# backplane.net
KiCad netlist of a schematic drawn in EAGLE
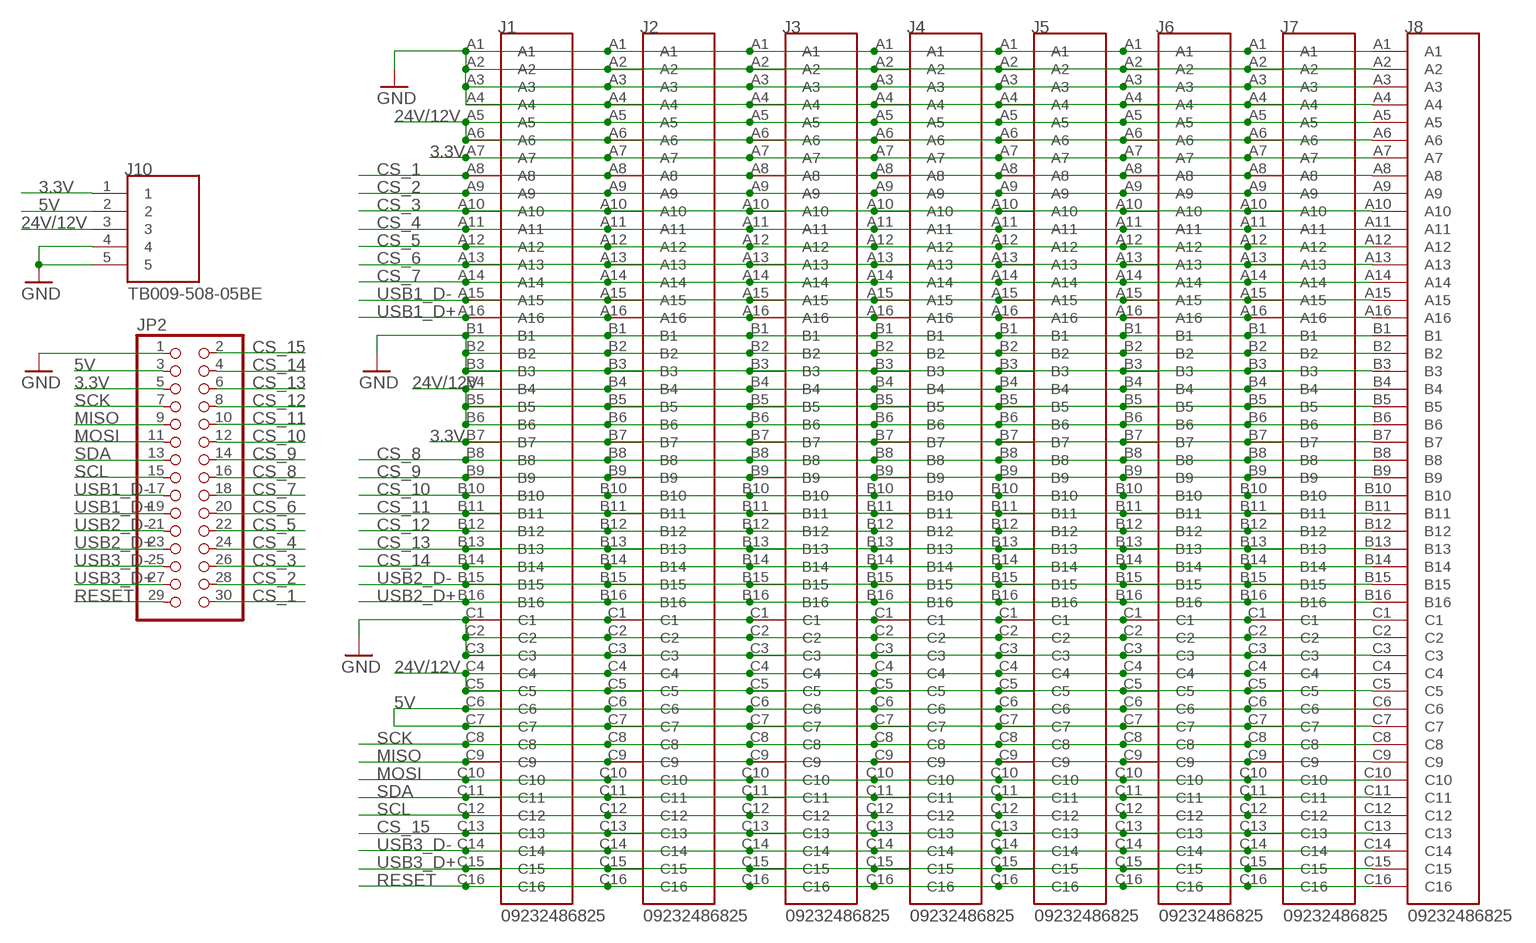
[diagram p0: schematic, sheet 1]

(export (version "E")
  (design (tool "Eeschema 10.0.6"))
  (components
    (comp (ref "J1")
      (value "09232486825")
      (footprint "eagle-import:HARTING_09232486825")
      (libsource (lib "eagle-import") (part "09232486825"))
    )
    (comp (ref "J2")
      (value "09232486825")
      (footprint "eagle-import:HARTING_09232486825")
      (libsource (lib "eagle-import") (part "09232486825"))
    )
    (comp (ref "J3")
      (value "09232486825")
      (footprint "eagle-import:HARTING_09232486825")
      (libsource (lib "eagle-import") (part "09232486825"))
    )
    (comp (ref "J4")
      (value "09232486825")
      (footprint "eagle-import:HARTING_09232486825")
      (libsource (lib "eagle-import") (part "09232486825"))
    )
    (comp (ref "J5")
      (value "09232486825")
      (footprint "eagle-import:HARTING_09232486825")
      (libsource (lib "eagle-import") (part "09232486825"))
    )
    (comp (ref "J6")
      (value "09232486825")
      (footprint "eagle-import:HARTING_09232486825")
      (libsource (lib "eagle-import") (part "09232486825"))
    )
    (comp (ref "J7")
      (value "09232486825")
      (footprint "eagle-import:HARTING_09232486825")
      (libsource (lib "eagle-import") (part "09232486825"))
    )
    (comp (ref "J8")
      (value "09232486825")
      (footprint "eagle-import:HARTING_09232486825")
      (libsource (lib "eagle-import") (part "09232486825"))
    )
    (comp (ref "J10")
      (value "TB009-508-05BE")
      (footprint "eagle-import:CUI_TB009-508-05BE")
      (libsource (lib "eagle-import") (part "TB009-508-05BE"))
    )
    (comp (ref "JP2")
      (value "PINHD-2X15")
      (footprint "eagle-import:2X15")
      (libsource (lib "eagle-import") (part "PINHD-2X15"))
    )
  )
  (nets
    (net (code "1") (name "/3.3V") (class "Default")
      (node (ref "J1") (pin "A7") (pinfunction "A7_A7") (pintype "passive"))
      (node (ref "J1") (pin "B7") (pinfunction "B7_B7") (pintype "passive"))
      (node (ref "J10") (pin "1") (pinfunction "1_1") (pintype "passive"))
      (node (ref "J2") (pin "A7") (pinfunction "A7_A7") (pintype "passive"))
      (node (ref "J2") (pin "B7") (pinfunction "B7_B7") (pintype "passive"))
      (node (ref "J3") (pin "A7") (pinfunction "A7_A7") (pintype "passive"))
      (node (ref "J3") (pin "B7") (pinfunction "B7_B7") (pintype "passive"))
      (node (ref "J4") (pin "A7") (pinfunction "A7_A7") (pintype "passive"))
      (node (ref "J4") (pin "B7") (pinfunction "B7_B7") (pintype "passive"))
      (node (ref "J5") (pin "A7") (pinfunction "A7_A7") (pintype "passive"))
      (node (ref "J5") (pin "B7") (pinfunction "B7_B7") (pintype "passive"))
      (node (ref "J6") (pin "A7") (pinfunction "A7_A7") (pintype "passive"))
      (node (ref "J6") (pin "B7") (pinfunction "B7_B7") (pintype "passive"))
      (node (ref "J7") (pin "A7") (pinfunction "A7_A7") (pintype "passive"))
      (node (ref "J7") (pin "B7") (pinfunction "B7_B7") (pintype "passive"))
      (node (ref "J8") (pin "A7") (pinfunction "A7_A7") (pintype "passive"))
      (node (ref "J8") (pin "B7") (pinfunction "B7_B7") (pintype "passive"))
      (node (ref "JP2") (pin "5") (pinfunction "5_5") (pintype "passive"))
    )
    (net (code "2") (name "/5V") (class "Default")
      (node (ref "J1") (pin "C6") (pinfunction "C6_C6") (pintype "passive"))
      (node (ref "J1") (pin "C7") (pinfunction "C7_C7") (pintype "passive"))
      (node (ref "J10") (pin "2") (pinfunction "2_2") (pintype "passive"))
      (node (ref "J2") (pin "C6") (pinfunction "C6_C6") (pintype "passive"))
      (node (ref "J2") (pin "C7") (pinfunction "C7_C7") (pintype "passive"))
      (node (ref "J3") (pin "C6") (pinfunction "C6_C6") (pintype "passive"))
      (node (ref "J3") (pin "C7") (pinfunction "C7_C7") (pintype "passive"))
      (node (ref "J4") (pin "C6") (pinfunction "C6_C6") (pintype "passive"))
      (node (ref "J4") (pin "C7") (pinfunction "C7_C7") (pintype "passive"))
      (node (ref "J5") (pin "C6") (pinfunction "C6_C6") (pintype "passive"))
      (node (ref "J5") (pin "C7") (pinfunction "C7_C7") (pintype "passive"))
      (node (ref "J6") (pin "C6") (pinfunction "C6_C6") (pintype "passive"))
      (node (ref "J6") (pin "C7") (pinfunction "C7_C7") (pintype "passive"))
      (node (ref "J7") (pin "C6") (pinfunction "C6_C6") (pintype "passive"))
      (node (ref "J7") (pin "C7") (pinfunction "C7_C7") (pintype "passive"))
      (node (ref "J8") (pin "C6") (pinfunction "C6_C6") (pintype "passive"))
      (node (ref "J8") (pin "C7") (pinfunction "C7_C7") (pintype "passive"))
      (node (ref "JP2") (pin "3") (pinfunction "3_3") (pintype "passive"))
    )
    (net (code "3") (name "/24V{slash}12V") (class "Default")
      (node (ref "J1") (pin "A5") (pinfunction "A5_A5") (pintype "passive"))
      (node (ref "J1") (pin "A6") (pinfunction "A6_A6") (pintype "passive"))
      (node (ref "J1") (pin "B4") (pinfunction "B4_B4") (pintype "passive"))
      (node (ref "J1") (pin "B5") (pinfunction "B5_B5") (pintype "passive"))
      (node (ref "J1") (pin "B6") (pinfunction "B6_B6") (pintype "passive"))
      (node (ref "J1") (pin "C4") (pinfunction "C4_C4") (pintype "passive"))
      (node (ref "J1") (pin "C5") (pinfunction "C5_C5") (pintype "passive"))
      (node (ref "J10") (pin "3") (pinfunction "3_3") (pintype "passive"))
      (node (ref "J2") (pin "A5") (pinfunction "A5_A5") (pintype "passive"))
      (node (ref "J2") (pin "A6") (pinfunction "A6_A6") (pintype "passive"))
      (node (ref "J2") (pin "B4") (pinfunction "B4_B4") (pintype "passive"))
      (node (ref "J2") (pin "B5") (pinfunction "B5_B5") (pintype "passive"))
      (node (ref "J2") (pin "B6") (pinfunction "B6_B6") (pintype "passive"))
      (node (ref "J2") (pin "C4") (pinfunction "C4_C4") (pintype "passive"))
      (node (ref "J2") (pin "C5") (pinfunction "C5_C5") (pintype "passive"))
      (node (ref "J3") (pin "A5") (pinfunction "A5_A5") (pintype "passive"))
      (node (ref "J3") (pin "A6") (pinfunction "A6_A6") (pintype "passive"))
      (node (ref "J3") (pin "B4") (pinfunction "B4_B4") (pintype "passive"))
      (node (ref "J3") (pin "B5") (pinfunction "B5_B5") (pintype "passive"))
      (node (ref "J3") (pin "B6") (pinfunction "B6_B6") (pintype "passive"))
      (node (ref "J3") (pin "C4") (pinfunction "C4_C4") (pintype "passive"))
      (node (ref "J3") (pin "C5") (pinfunction "C5_C5") (pintype "passive"))
      (node (ref "J4") (pin "A5") (pinfunction "A5_A5") (pintype "passive"))
      (node (ref "J4") (pin "A6") (pinfunction "A6_A6") (pintype "passive"))
      (node (ref "J4") (pin "B4") (pinfunction "B4_B4") (pintype "passive"))
      (node (ref "J4") (pin "B5") (pinfunction "B5_B5") (pintype "passive"))
      (node (ref "J4") (pin "B6") (pinfunction "B6_B6") (pintype "passive"))
      (node (ref "J4") (pin "C4") (pinfunction "C4_C4") (pintype "passive"))
      (node (ref "J4") (pin "C5") (pinfunction "C5_C5") (pintype "passive"))
      (node (ref "J5") (pin "A5") (pinfunction "A5_A5") (pintype "passive"))
      (node (ref "J5") (pin "A6") (pinfunction "A6_A6") (pintype "passive"))
      (node (ref "J5") (pin "B4") (pinfunction "B4_B4") (pintype "passive"))
      (node (ref "J5") (pin "B5") (pinfunction "B5_B5") (pintype "passive"))
      (node (ref "J5") (pin "B6") (pinfunction "B6_B6") (pintype "passive"))
      (node (ref "J5") (pin "C4") (pinfunction "C4_C4") (pintype "passive"))
      (node (ref "J5") (pin "C5") (pinfunction "C5_C5") (pintype "passive"))
      (node (ref "J6") (pin "A5") (pinfunction "A5_A5") (pintype "passive"))
      (node (ref "J6") (pin "A6") (pinfunction "A6_A6") (pintype "passive"))
      (node (ref "J6") (pin "B4") (pinfunction "B4_B4") (pintype "passive"))
      (node (ref "J6") (pin "B5") (pinfunction "B5_B5") (pintype "passive"))
      (node (ref "J6") (pin "B6") (pinfunction "B6_B6") (pintype "passive"))
      (node (ref "J6") (pin "C4") (pinfunction "C4_C4") (pintype "passive"))
      (node (ref "J6") (pin "C5") (pinfunction "C5_C5") (pintype "passive"))
      (node (ref "J7") (pin "A5") (pinfunction "A5_A5") (pintype "passive"))
      (node (ref "J7") (pin "A6") (pinfunction "A6_A6") (pintype "passive"))
      (node (ref "J7") (pin "B4") (pinfunction "B4_B4") (pintype "passive"))
      (node (ref "J7") (pin "B5") (pinfunction "B5_B5") (pintype "passive"))
      (node (ref "J7") (pin "B6") (pinfunction "B6_B6") (pintype "passive"))
      (node (ref "J7") (pin "C4") (pinfunction "C4_C4") (pintype "passive"))
      (node (ref "J7") (pin "C5") (pinfunction "C5_C5") (pintype "passive"))
      (node (ref "J8") (pin "A5") (pinfunction "A5_A5") (pintype "passive"))
      (node (ref "J8") (pin "A6") (pinfunction "A6_A6") (pintype "passive"))
      (node (ref "J8") (pin "B4") (pinfunction "B4_B4") (pintype "passive"))
      (node (ref "J8") (pin "B5") (pinfunction "B5_B5") (pintype "passive"))
      (node (ref "J8") (pin "B6") (pinfunction "B6_B6") (pintype "passive"))
      (node (ref "J8") (pin "C4") (pinfunction "C4_C4") (pintype "passive"))
      (node (ref "J8") (pin "C5") (pinfunction "C5_C5") (pintype "passive"))
    )
    (net (code "4") (name "/CS_1") (class "Default")
      (node (ref "J1") (pin "A8") (pinfunction "A8_A8") (pintype "passive"))
      (node (ref "J2") (pin "A8") (pinfunction "A8_A8") (pintype "passive"))
      (node (ref "J3") (pin "A8") (pinfunction "A8_A8") (pintype "passive"))
      (node (ref "J4") (pin "A8") (pinfunction "A8_A8") (pintype "passive"))
      (node (ref "J5") (pin "A8") (pinfunction "A8_A8") (pintype "passive"))
      (node (ref "J6") (pin "A8") (pinfunction "A8_A8") (pintype "passive"))
      (node (ref "J7") (pin "A8") (pinfunction "A8_A8") (pintype "passive"))
      (node (ref "J8") (pin "A8") (pinfunction "A8_A8") (pintype "passive"))
      (node (ref "JP2") (pin "30") (pinfunction "30_30") (pintype "passive"))
    )
    (net (code "5") (name "/CS_2") (class "Default")
      (node (ref "J1") (pin "A9") (pinfunction "A9_A9") (pintype "passive"))
      (node (ref "J2") (pin "A9") (pinfunction "A9_A9") (pintype "passive"))
      (node (ref "J3") (pin "A9") (pinfunction "A9_A9") (pintype "passive"))
      (node (ref "J4") (pin "A9") (pinfunction "A9_A9") (pintype "passive"))
      (node (ref "J5") (pin "A9") (pinfunction "A9_A9") (pintype "passive"))
      (node (ref "J6") (pin "A9") (pinfunction "A9_A9") (pintype "passive"))
      (node (ref "J7") (pin "A9") (pinfunction "A9_A9") (pintype "passive"))
      (node (ref "J8") (pin "A9") (pinfunction "A9_A9") (pintype "passive"))
      (node (ref "JP2") (pin "28") (pinfunction "28_28") (pintype "passive"))
    )
    (net (code "6") (name "/CS_3") (class "Default")
      (node (ref "J1") (pin "A10") (pinfunction "A10_A10") (pintype "passive"))
      (node (ref "J2") (pin "A10") (pinfunction "A10_A10") (pintype "passive"))
      (node (ref "J3") (pin "A10") (pinfunction "A10_A10") (pintype "passive"))
      (node (ref "J4") (pin "A10") (pinfunction "A10_A10") (pintype "passive"))
      (node (ref "J5") (pin "A10") (pinfunction "A10_A10") (pintype "passive"))
      (node (ref "J6") (pin "A10") (pinfunction "A10_A10") (pintype "passive"))
      (node (ref "J7") (pin "A10") (pinfunction "A10_A10") (pintype "passive"))
      (node (ref "J8") (pin "A10") (pinfunction "A10_A10") (pintype "passive"))
      (node (ref "JP2") (pin "26") (pinfunction "26_26") (pintype "passive"))
    )
    (net (code "7") (name "/CS_4") (class "Default")
      (node (ref "J1") (pin "A11") (pinfunction "A11_A11") (pintype "passive"))
      (node (ref "J2") (pin "A11") (pinfunction "A11_A11") (pintype "passive"))
      (node (ref "J3") (pin "A11") (pinfunction "A11_A11") (pintype "passive"))
      (node (ref "J4") (pin "A11") (pinfunction "A11_A11") (pintype "passive"))
      (node (ref "J5") (pin "A11") (pinfunction "A11_A11") (pintype "passive"))
      (node (ref "J6") (pin "A11") (pinfunction "A11_A11") (pintype "passive"))
      (node (ref "J7") (pin "A11") (pinfunction "A11_A11") (pintype "passive"))
      (node (ref "J8") (pin "A11") (pinfunction "A11_A11") (pintype "passive"))
      (node (ref "JP2") (pin "24") (pinfunction "24_24") (pintype "passive"))
    )
    (net (code "8") (name "/CS_5") (class "Default")
      (node (ref "J1") (pin "A12") (pinfunction "A12_A12") (pintype "passive"))
      (node (ref "J2") (pin "A12") (pinfunction "A12_A12") (pintype "passive"))
      (node (ref "J3") (pin "A12") (pinfunction "A12_A12") (pintype "passive"))
      (node (ref "J4") (pin "A12") (pinfunction "A12_A12") (pintype "passive"))
      (node (ref "J5") (pin "A12") (pinfunction "A12_A12") (pintype "passive"))
      (node (ref "J6") (pin "A12") (pinfunction "A12_A12") (pintype "passive"))
      (node (ref "J7") (pin "A12") (pinfunction "A12_A12") (pintype "passive"))
      (node (ref "J8") (pin "A12") (pinfunction "A12_A12") (pintype "passive"))
      (node (ref "JP2") (pin "22") (pinfunction "22_22") (pintype "passive"))
    )
    (net (code "9") (name "/CS_6") (class "Default")
      (node (ref "J1") (pin "A13") (pinfunction "A13_A13") (pintype "passive"))
      (node (ref "J2") (pin "A13") (pinfunction "A13_A13") (pintype "passive"))
      (node (ref "J3") (pin "A13") (pinfunction "A13_A13") (pintype "passive"))
      (node (ref "J4") (pin "A13") (pinfunction "A13_A13") (pintype "passive"))
      (node (ref "J5") (pin "A13") (pinfunction "A13_A13") (pintype "passive"))
      (node (ref "J6") (pin "A13") (pinfunction "A13_A13") (pintype "passive"))
      (node (ref "J7") (pin "A13") (pinfunction "A13_A13") (pintype "passive"))
      (node (ref "J8") (pin "A13") (pinfunction "A13_A13") (pintype "passive"))
      (node (ref "JP2") (pin "20") (pinfunction "20_20") (pintype "passive"))
    )
    (net (code "10") (name "/CS_7") (class "Default")
      (node (ref "J1") (pin "A14") (pinfunction "A14_A14") (pintype "passive"))
      (node (ref "J2") (pin "A14") (pinfunction "A14_A14") (pintype "passive"))
      (node (ref "J3") (pin "A14") (pinfunction "A14_A14") (pintype "passive"))
      (node (ref "J4") (pin "A14") (pinfunction "A14_A14") (pintype "passive"))
      (node (ref "J5") (pin "A14") (pinfunction "A14_A14") (pintype "passive"))
      (node (ref "J6") (pin "A14") (pinfunction "A14_A14") (pintype "passive"))
      (node (ref "J7") (pin "A14") (pinfunction "A14_A14") (pintype "passive"))
      (node (ref "J8") (pin "A14") (pinfunction "A14_A14") (pintype "passive"))
      (node (ref "JP2") (pin "18") (pinfunction "18_18") (pintype "passive"))
    )
    (net (code "11") (name "/CS_8") (class "Default")
      (node (ref "J1") (pin "B8") (pinfunction "B8_B8") (pintype "passive"))
      (node (ref "J2") (pin "B8") (pinfunction "B8_B8") (pintype "passive"))
      (node (ref "J3") (pin "B8") (pinfunction "B8_B8") (pintype "passive"))
      (node (ref "J4") (pin "B8") (pinfunction "B8_B8") (pintype "passive"))
      (node (ref "J5") (pin "B8") (pinfunction "B8_B8") (pintype "passive"))
      (node (ref "J6") (pin "B8") (pinfunction "B8_B8") (pintype "passive"))
      (node (ref "J7") (pin "B8") (pinfunction "B8_B8") (pintype "passive"))
      (node (ref "J8") (pin "B8") (pinfunction "B8_B8") (pintype "passive"))
      (node (ref "JP2") (pin "16") (pinfunction "16_16") (pintype "passive"))
    )
    (net (code "12") (name "/CS_9") (class "Default")
      (node (ref "J1") (pin "B9") (pinfunction "B9_B9") (pintype "passive"))
      (node (ref "J2") (pin "B9") (pinfunction "B9_B9") (pintype "passive"))
      (node (ref "J3") (pin "B9") (pinfunction "B9_B9") (pintype "passive"))
      (node (ref "J4") (pin "B9") (pinfunction "B9_B9") (pintype "passive"))
      (node (ref "J5") (pin "B9") (pinfunction "B9_B9") (pintype "passive"))
      (node (ref "J6") (pin "B9") (pinfunction "B9_B9") (pintype "passive"))
      (node (ref "J7") (pin "B9") (pinfunction "B9_B9") (pintype "passive"))
      (node (ref "J8") (pin "B9") (pinfunction "B9_B9") (pintype "passive"))
      (node (ref "JP2") (pin "14") (pinfunction "14_14") (pintype "passive"))
    )
    (net (code "13") (name "/CS_10") (class "Default")
      (node (ref "J1") (pin "B10") (pinfunction "B10_B10") (pintype "passive"))
      (node (ref "J2") (pin "B10") (pinfunction "B10_B10") (pintype "passive"))
      (node (ref "J3") (pin "B10") (pinfunction "B10_B10") (pintype "passive"))
      (node (ref "J4") (pin "B10") (pinfunction "B10_B10") (pintype "passive"))
      (node (ref "J5") (pin "B10") (pinfunction "B10_B10") (pintype "passive"))
      (node (ref "J6") (pin "B10") (pinfunction "B10_B10") (pintype "passive"))
      (node (ref "J7") (pin "B10") (pinfunction "B10_B10") (pintype "passive"))
      (node (ref "J8") (pin "B10") (pinfunction "B10_B10") (pintype "passive"))
      (node (ref "JP2") (pin "12") (pinfunction "12_12") (pintype "passive"))
    )
    (net (code "14") (name "/CS_11") (class "Default")
      (node (ref "J1") (pin "B11") (pinfunction "B11_B11") (pintype "passive"))
      (node (ref "J2") (pin "B11") (pinfunction "B11_B11") (pintype "passive"))
      (node (ref "J3") (pin "B11") (pinfunction "B11_B11") (pintype "passive"))
      (node (ref "J4") (pin "B11") (pinfunction "B11_B11") (pintype "passive"))
      (node (ref "J5") (pin "B11") (pinfunction "B11_B11") (pintype "passive"))
      (node (ref "J6") (pin "B11") (pinfunction "B11_B11") (pintype "passive"))
      (node (ref "J7") (pin "B11") (pinfunction "B11_B11") (pintype "passive"))
      (node (ref "J8") (pin "B11") (pinfunction "B11_B11") (pintype "passive"))
      (node (ref "JP2") (pin "10") (pinfunction "10_10") (pintype "passive"))
    )
    (net (code "15") (name "/CS_12") (class "Default")
      (node (ref "J1") (pin "B12") (pinfunction "B12_B12") (pintype "passive"))
      (node (ref "J2") (pin "B12") (pinfunction "B12_B12") (pintype "passive"))
      (node (ref "J3") (pin "B12") (pinfunction "B12_B12") (pintype "passive"))
      (node (ref "J4") (pin "B12") (pinfunction "B12_B12") (pintype "passive"))
      (node (ref "J5") (pin "B12") (pinfunction "B12_B12") (pintype "passive"))
      (node (ref "J6") (pin "B12") (pinfunction "B12_B12") (pintype "passive"))
      (node (ref "J7") (pin "B12") (pinfunction "B12_B12") (pintype "passive"))
      (node (ref "J8") (pin "B12") (pinfunction "B12_B12") (pintype "passive"))
      (node (ref "JP2") (pin "8") (pinfunction "8_8") (pintype "passive"))
    )
    (net (code "16") (name "/CS_13") (class "Default")
      (node (ref "J1") (pin "B13") (pinfunction "B13_B13") (pintype "passive"))
      (node (ref "J2") (pin "B13") (pinfunction "B13_B13") (pintype "passive"))
      (node (ref "J3") (pin "B13") (pinfunction "B13_B13") (pintype "passive"))
      (node (ref "J4") (pin "B13") (pinfunction "B13_B13") (pintype "passive"))
      (node (ref "J5") (pin "B13") (pinfunction "B13_B13") (pintype "passive"))
      (node (ref "J6") (pin "B13") (pinfunction "B13_B13") (pintype "passive"))
      (node (ref "J7") (pin "B13") (pinfunction "B13_B13") (pintype "passive"))
      (node (ref "J8") (pin "B13") (pinfunction "B13_B13") (pintype "passive"))
      (node (ref "JP2") (pin "6") (pinfunction "6_6") (pintype "passive"))
    )
    (net (code "17") (name "/CS_14") (class "Default")
      (node (ref "J1") (pin "B14") (pinfunction "B14_B14") (pintype "passive"))
      (node (ref "J2") (pin "B14") (pinfunction "B14_B14") (pintype "passive"))
      (node (ref "J3") (pin "B14") (pinfunction "B14_B14") (pintype "passive"))
      (node (ref "J4") (pin "B14") (pinfunction "B14_B14") (pintype "passive"))
      (node (ref "J5") (pin "B14") (pinfunction "B14_B14") (pintype "passive"))
      (node (ref "J6") (pin "B14") (pinfunction "B14_B14") (pintype "passive"))
      (node (ref "J7") (pin "B14") (pinfunction "B14_B14") (pintype "passive"))
      (node (ref "J8") (pin "B14") (pinfunction "B14_B14") (pintype "passive"))
      (node (ref "JP2") (pin "4") (pinfunction "4_4") (pintype "passive"))
    )
    (net (code "18") (name "/CS_15") (class "Default")
      (node (ref "J1") (pin "C13") (pinfunction "C13_C13") (pintype "passive"))
      (node (ref "J2") (pin "C13") (pinfunction "C13_C13") (pintype "passive"))
      (node (ref "J3") (pin "C13") (pinfunction "C13_C13") (pintype "passive"))
      (node (ref "J4") (pin "C13") (pinfunction "C13_C13") (pintype "passive"))
      (node (ref "J5") (pin "C13") (pinfunction "C13_C13") (pintype "passive"))
      (node (ref "J6") (pin "C13") (pinfunction "C13_C13") (pintype "passive"))
      (node (ref "J7") (pin "C13") (pinfunction "C13_C13") (pintype "passive"))
      (node (ref "J8") (pin "C13") (pinfunction "C13_C13") (pintype "passive"))
      (node (ref "JP2") (pin "2") (pinfunction "2_2") (pintype "passive"))
    )
    (net (code "19") (name "/MISO") (class "Default")
      (node (ref "J1") (pin "C9") (pinfunction "C9_C9") (pintype "passive"))
      (node (ref "J2") (pin "C9") (pinfunction "C9_C9") (pintype "passive"))
      (node (ref "J3") (pin "C9") (pinfunction "C9_C9") (pintype "passive"))
      (node (ref "J4") (pin "C9") (pinfunction "C9_C9") (pintype "passive"))
      (node (ref "J5") (pin "C9") (pinfunction "C9_C9") (pintype "passive"))
      (node (ref "J6") (pin "C9") (pinfunction "C9_C9") (pintype "passive"))
      (node (ref "J7") (pin "C9") (pinfunction "C9_C9") (pintype "passive"))
      (node (ref "J8") (pin "C9") (pinfunction "C9_C9") (pintype "passive"))
      (node (ref "JP2") (pin "9") (pinfunction "9_9") (pintype "passive"))
    )
    (net (code "20") (name "/MOSI") (class "Default")
      (node (ref "J1") (pin "C10") (pinfunction "C10_C10") (pintype "passive"))
      (node (ref "J2") (pin "C10") (pinfunction "C10_C10") (pintype "passive"))
      (node (ref "J3") (pin "C10") (pinfunction "C10_C10") (pintype "passive"))
      (node (ref "J4") (pin "C10") (pinfunction "C10_C10") (pintype "passive"))
      (node (ref "J5") (pin "C10") (pinfunction "C10_C10") (pintype "passive"))
      (node (ref "J6") (pin "C10") (pinfunction "C10_C10") (pintype "passive"))
      (node (ref "J7") (pin "C10") (pinfunction "C10_C10") (pintype "passive"))
      (node (ref "J8") (pin "C10") (pinfunction "C10_C10") (pintype "passive"))
      (node (ref "JP2") (pin "11") (pinfunction "11_11") (pintype "passive"))
    )
    (net (code "21") (name "/RESET") (class "Default")
      (node (ref "J1") (pin "C16") (pinfunction "C16_C16") (pintype "passive"))
      (node (ref "J2") (pin "C16") (pinfunction "C16_C16") (pintype "passive"))
      (node (ref "J3") (pin "C16") (pinfunction "C16_C16") (pintype "passive"))
      (node (ref "J4") (pin "C16") (pinfunction "C16_C16") (pintype "passive"))
      (node (ref "J5") (pin "C16") (pinfunction "C16_C16") (pintype "passive"))
      (node (ref "J6") (pin "C16") (pinfunction "C16_C16") (pintype "passive"))
      (node (ref "J7") (pin "C16") (pinfunction "C16_C16") (pintype "passive"))
      (node (ref "J8") (pin "C16") (pinfunction "C16_C16") (pintype "passive"))
      (node (ref "JP2") (pin "29") (pinfunction "29_29") (pintype "passive"))
    )
    (net (code "22") (name "/SCK") (class "Default")
      (node (ref "J1") (pin "C8") (pinfunction "C8_C8") (pintype "passive"))
      (node (ref "J2") (pin "C8") (pinfunction "C8_C8") (pintype "passive"))
      (node (ref "J3") (pin "C8") (pinfunction "C8_C8") (pintype "passive"))
      (node (ref "J4") (pin "C8") (pinfunction "C8_C8") (pintype "passive"))
      (node (ref "J5") (pin "C8") (pinfunction "C8_C8") (pintype "passive"))
      (node (ref "J6") (pin "C8") (pinfunction "C8_C8") (pintype "passive"))
      (node (ref "J7") (pin "C8") (pinfunction "C8_C8") (pintype "passive"))
      (node (ref "J8") (pin "C8") (pinfunction "C8_C8") (pintype "passive"))
      (node (ref "JP2") (pin "7") (pinfunction "7_7") (pintype "passive"))
    )
    (net (code "23") (name "/SCL") (class "Default")
      (node (ref "J1") (pin "C12") (pinfunction "C12_C12") (pintype "passive"))
      (node (ref "J2") (pin "C12") (pinfunction "C12_C12") (pintype "passive"))
      (node (ref "J3") (pin "C12") (pinfunction "C12_C12") (pintype "passive"))
      (node (ref "J4") (pin "C12") (pinfunction "C12_C12") (pintype "passive"))
      (node (ref "J5") (pin "C12") (pinfunction "C12_C12") (pintype "passive"))
      (node (ref "J6") (pin "C12") (pinfunction "C12_C12") (pintype "passive"))
      (node (ref "J7") (pin "C12") (pinfunction "C12_C12") (pintype "passive"))
      (node (ref "J8") (pin "C12") (pinfunction "C12_C12") (pintype "passive"))
      (node (ref "JP2") (pin "15") (pinfunction "15_15") (pintype "passive"))
    )
    (net (code "24") (name "/SDA") (class "Default")
      (node (ref "J1") (pin "C11") (pinfunction "C11_C11") (pintype "passive"))
      (node (ref "J2") (pin "C11") (pinfunction "C11_C11") (pintype "passive"))
      (node (ref "J3") (pin "C11") (pinfunction "C11_C11") (pintype "passive"))
      (node (ref "J4") (pin "C11") (pinfunction "C11_C11") (pintype "passive"))
      (node (ref "J5") (pin "C11") (pinfunction "C11_C11") (pintype "passive"))
      (node (ref "J6") (pin "C11") (pinfunction "C11_C11") (pintype "passive"))
      (node (ref "J7") (pin "C11") (pinfunction "C11_C11") (pintype "passive"))
      (node (ref "J8") (pin "C11") (pinfunction "C11_C11") (pintype "passive"))
      (node (ref "JP2") (pin "13") (pinfunction "13_13") (pintype "passive"))
    )
    (net (code "25") (name "/USB1_D+") (class "Default")
      (node (ref "J1") (pin "A16") (pinfunction "A16_A16") (pintype "passive"))
      (node (ref "J2") (pin "A16") (pinfunction "A16_A16") (pintype "passive"))
      (node (ref "J3") (pin "A16") (pinfunction "A16_A16") (pintype "passive"))
      (node (ref "J4") (pin "A16") (pinfunction "A16_A16") (pintype "passive"))
      (node (ref "J5") (pin "A16") (pinfunction "A16_A16") (pintype "passive"))
      (node (ref "J6") (pin "A16") (pinfunction "A16_A16") (pintype "passive"))
      (node (ref "J7") (pin "A16") (pinfunction "A16_A16") (pintype "passive"))
      (node (ref "J8") (pin "A16") (pinfunction "A16_A16") (pintype "passive"))
      (node (ref "JP2") (pin "19") (pinfunction "19_19") (pintype "passive"))
    )
    (net (code "26") (name "/USB1_D-") (class "Default")
      (node (ref "J1") (pin "A15") (pinfunction "A15_A15") (pintype "passive"))
      (node (ref "J2") (pin "A15") (pinfunction "A15_A15") (pintype "passive"))
      (node (ref "J3") (pin "A15") (pinfunction "A15_A15") (pintype "passive"))
      (node (ref "J4") (pin "A15") (pinfunction "A15_A15") (pintype "passive"))
      (node (ref "J5") (pin "A15") (pinfunction "A15_A15") (pintype "passive"))
      (node (ref "J6") (pin "A15") (pinfunction "A15_A15") (pintype "passive"))
      (node (ref "J7") (pin "A15") (pinfunction "A15_A15") (pintype "passive"))
      (node (ref "J8") (pin "A15") (pinfunction "A15_A15") (pintype "passive"))
      (node (ref "JP2") (pin "17") (pinfunction "17_17") (pintype "passive"))
    )
    (net (code "27") (name "/USB2_D+") (class "Default")
      (node (ref "J1") (pin "B16") (pinfunction "B16_B16") (pintype "passive"))
      (node (ref "J2") (pin "B16") (pinfunction "B16_B16") (pintype "passive"))
      (node (ref "J3") (pin "B16") (pinfunction "B16_B16") (pintype "passive"))
      (node (ref "J4") (pin "B16") (pinfunction "B16_B16") (pintype "passive"))
      (node (ref "J5") (pin "B16") (pinfunction "B16_B16") (pintype "passive"))
      (node (ref "J6") (pin "B16") (pinfunction "B16_B16") (pintype "passive"))
      (node (ref "J7") (pin "B16") (pinfunction "B16_B16") (pintype "passive"))
      (node (ref "J8") (pin "B16") (pinfunction "B16_B16") (pintype "passive"))
      (node (ref "JP2") (pin "23") (pinfunction "23_23") (pintype "passive"))
    )
    (net (code "28") (name "/USB2_D-") (class "Default")
      (node (ref "J1") (pin "B15") (pinfunction "B15_B15") (pintype "passive"))
      (node (ref "J2") (pin "B15") (pinfunction "B15_B15") (pintype "passive"))
      (node (ref "J3") (pin "B15") (pinfunction "B15_B15") (pintype "passive"))
      (node (ref "J4") (pin "B15") (pinfunction "B15_B15") (pintype "passive"))
      (node (ref "J5") (pin "B15") (pinfunction "B15_B15") (pintype "passive"))
      (node (ref "J6") (pin "B15") (pinfunction "B15_B15") (pintype "passive"))
      (node (ref "J7") (pin "B15") (pinfunction "B15_B15") (pintype "passive"))
      (node (ref "J8") (pin "B15") (pinfunction "B15_B15") (pintype "passive"))
      (node (ref "JP2") (pin "21") (pinfunction "21_21") (pintype "passive"))
    )
    (net (code "29") (name "/USB3_D+") (class "Default")
      (node (ref "J1") (pin "C15") (pinfunction "C15_C15") (pintype "passive"))
      (node (ref "J2") (pin "C15") (pinfunction "C15_C15") (pintype "passive"))
      (node (ref "J3") (pin "C15") (pinfunction "C15_C15") (pintype "passive"))
      (node (ref "J4") (pin "C15") (pinfunction "C15_C15") (pintype "passive"))
      (node (ref "J5") (pin "C15") (pinfunction "C15_C15") (pintype "passive"))
      (node (ref "J6") (pin "C15") (pinfunction "C15_C15") (pintype "passive"))
      (node (ref "J7") (pin "C15") (pinfunction "C15_C15") (pintype "passive"))
      (node (ref "J8") (pin "C15") (pinfunction "C15_C15") (pintype "passive"))
      (node (ref "JP2") (pin "27") (pinfunction "27_27") (pintype "passive"))
    )
    (net (code "30") (name "/USB3_D-") (class "Default")
      (node (ref "J1") (pin "C14") (pinfunction "C14_C14") (pintype "passive"))
      (node (ref "J2") (pin "C14") (pinfunction "C14_C14") (pintype "passive"))
      (node (ref "J3") (pin "C14") (pinfunction "C14_C14") (pintype "passive"))
      (node (ref "J4") (pin "C14") (pinfunction "C14_C14") (pintype "passive"))
      (node (ref "J5") (pin "C14") (pinfunction "C14_C14") (pintype "passive"))
      (node (ref "J6") (pin "C14") (pinfunction "C14_C14") (pintype "passive"))
      (node (ref "J7") (pin "C14") (pinfunction "C14_C14") (pintype "passive"))
      (node (ref "J8") (pin "C14") (pinfunction "C14_C14") (pintype "passive"))
      (node (ref "JP2") (pin "25") (pinfunction "25_25") (pintype "passive"))
    )
    (net (code "31") (name "GND") (class "Default")
      (node (ref "J1") (pin "A1") (pinfunction "A1_A1") (pintype "passive"))
      (node (ref "J1") (pin "A2") (pinfunction "A2_A2") (pintype "passive"))
      (node (ref "J1") (pin "A3") (pinfunction "A3_A3") (pintype "passive"))
      (node (ref "J1") (pin "A4") (pinfunction "A4_A4") (pintype "passive"))
      (node (ref "J1") (pin "B1") (pinfunction "B1_B1") (pintype "passive"))
      (node (ref "J1") (pin "B2") (pinfunction "B2_B2") (pintype "passive"))
      (node (ref "J1") (pin "B3") (pinfunction "B3_B3") (pintype "passive"))
      (node (ref "J1") (pin "C1") (pinfunction "C1_C1") (pintype "passive"))
      (node (ref "J1") (pin "C2") (pinfunction "C2_C2") (pintype "passive"))
      (node (ref "J1") (pin "C3") (pinfunction "C3_C3") (pintype "passive"))
      (node (ref "J10") (pin "4") (pinfunction "4_4") (pintype "passive"))
      (node (ref "J10") (pin "5") (pinfunction "5_5") (pintype "passive"))
      (node (ref "J2") (pin "A1") (pinfunction "A1_A1") (pintype "passive"))
      (node (ref "J2") (pin "A2") (pinfunction "A2_A2") (pintype "passive"))
      (node (ref "J2") (pin "A3") (pinfunction "A3_A3") (pintype "passive"))
      (node (ref "J2") (pin "A4") (pinfunction "A4_A4") (pintype "passive"))
      (node (ref "J2") (pin "B1") (pinfunction "B1_B1") (pintype "passive"))
      (node (ref "J2") (pin "B2") (pinfunction "B2_B2") (pintype "passive"))
      (node (ref "J2") (pin "B3") (pinfunction "B3_B3") (pintype "passive"))
      (node (ref "J2") (pin "C1") (pinfunction "C1_C1") (pintype "passive"))
      (node (ref "J2") (pin "C2") (pinfunction "C2_C2") (pintype "passive"))
      (node (ref "J2") (pin "C3") (pinfunction "C3_C3") (pintype "passive"))
      (node (ref "J3") (pin "A1") (pinfunction "A1_A1") (pintype "passive"))
      (node (ref "J3") (pin "A2") (pinfunction "A2_A2") (pintype "passive"))
      (node (ref "J3") (pin "A3") (pinfunction "A3_A3") (pintype "passive"))
      (node (ref "J3") (pin "A4") (pinfunction "A4_A4") (pintype "passive"))
      (node (ref "J3") (pin "B1") (pinfunction "B1_B1") (pintype "passive"))
      (node (ref "J3") (pin "B2") (pinfunction "B2_B2") (pintype "passive"))
      (node (ref "J3") (pin "B3") (pinfunction "B3_B3") (pintype "passive"))
      (node (ref "J3") (pin "C1") (pinfunction "C1_C1") (pintype "passive"))
      (node (ref "J3") (pin "C2") (pinfunction "C2_C2") (pintype "passive"))
      (node (ref "J3") (pin "C3") (pinfunction "C3_C3") (pintype "passive"))
      (node (ref "J4") (pin "A1") (pinfunction "A1_A1") (pintype "passive"))
      (node (ref "J4") (pin "A2") (pinfunction "A2_A2") (pintype "passive"))
      (node (ref "J4") (pin "A3") (pinfunction "A3_A3") (pintype "passive"))
      (node (ref "J4") (pin "A4") (pinfunction "A4_A4") (pintype "passive"))
      (node (ref "J4") (pin "B1") (pinfunction "B1_B1") (pintype "passive"))
      (node (ref "J4") (pin "B2") (pinfunction "B2_B2") (pintype "passive"))
      (node (ref "J4") (pin "B3") (pinfunction "B3_B3") (pintype "passive"))
      (node (ref "J4") (pin "C1") (pinfunction "C1_C1") (pintype "passive"))
      (node (ref "J4") (pin "C2") (pinfunction "C2_C2") (pintype "passive"))
      (node (ref "J4") (pin "C3") (pinfunction "C3_C3") (pintype "passive"))
      (node (ref "J5") (pin "A1") (pinfunction "A1_A1") (pintype "passive"))
      (node (ref "J5") (pin "A2") (pinfunction "A2_A2") (pintype "passive"))
      (node (ref "J5") (pin "A3") (pinfunction "A3_A3") (pintype "passive"))
      (node (ref "J5") (pin "A4") (pinfunction "A4_A4") (pintype "passive"))
      (node (ref "J5") (pin "B1") (pinfunction "B1_B1") (pintype "passive"))
      (node (ref "J5") (pin "B2") (pinfunction "B2_B2") (pintype "passive"))
      (node (ref "J5") (pin "B3") (pinfunction "B3_B3") (pintype "passive"))
      (node (ref "J5") (pin "C1") (pinfunction "C1_C1") (pintype "passive"))
      (node (ref "J5") (pin "C2") (pinfunction "C2_C2") (pintype "passive"))
      (node (ref "J5") (pin "C3") (pinfunction "C3_C3") (pintype "passive"))
      (node (ref "J6") (pin "A1") (pinfunction "A1_A1") (pintype "passive"))
      (node (ref "J6") (pin "A2") (pinfunction "A2_A2") (pintype "passive"))
      (node (ref "J6") (pin "A3") (pinfunction "A3_A3") (pintype "passive"))
      (node (ref "J6") (pin "A4") (pinfunction "A4_A4") (pintype "passive"))
      (node (ref "J6") (pin "B1") (pinfunction "B1_B1") (pintype "passive"))
      (node (ref "J6") (pin "B2") (pinfunction "B2_B2") (pintype "passive"))
      (node (ref "J6") (pin "B3") (pinfunction "B3_B3") (pintype "passive"))
      (node (ref "J6") (pin "C1") (pinfunction "C1_C1") (pintype "passive"))
      (node (ref "J6") (pin "C2") (pinfunction "C2_C2") (pintype "passive"))
      (node (ref "J6") (pin "C3") (pinfunction "C3_C3") (pintype "passive"))
      (node (ref "J7") (pin "A1") (pinfunction "A1_A1") (pintype "passive"))
      (node (ref "J7") (pin "A2") (pinfunction "A2_A2") (pintype "passive"))
      (node (ref "J7") (pin "A3") (pinfunction "A3_A3") (pintype "passive"))
      (node (ref "J7") (pin "A4") (pinfunction "A4_A4") (pintype "passive"))
      (node (ref "J7") (pin "B1") (pinfunction "B1_B1") (pintype "passive"))
      (node (ref "J7") (pin "B2") (pinfunction "B2_B2") (pintype "passive"))
      (node (ref "J7") (pin "B3") (pinfunction "B3_B3") (pintype "passive"))
      (node (ref "J7") (pin "C1") (pinfunction "C1_C1") (pintype "passive"))
      (node (ref "J7") (pin "C2") (pinfunction "C2_C2") (pintype "passive"))
      (node (ref "J7") (pin "C3") (pinfunction "C3_C3") (pintype "passive"))
      (node (ref "J8") (pin "A1") (pinfunction "A1_A1") (pintype "passive"))
      (node (ref "J8") (pin "A2") (pinfunction "A2_A2") (pintype "passive"))
      (node (ref "J8") (pin "A3") (pinfunction "A3_A3") (pintype "passive"))
      (node (ref "J8") (pin "A4") (pinfunction "A4_A4") (pintype "passive"))
      (node (ref "J8") (pin "B1") (pinfunction "B1_B1") (pintype "passive"))
      (node (ref "J8") (pin "B2") (pinfunction "B2_B2") (pintype "passive"))
      (node (ref "J8") (pin "B3") (pinfunction "B3_B3") (pintype "passive"))
      (node (ref "J8") (pin "C1") (pinfunction "C1_C1") (pintype "passive"))
      (node (ref "J8") (pin "C2") (pinfunction "C2_C2") (pintype "passive"))
      (node (ref "J8") (pin "C3") (pinfunction "C3_C3") (pintype "passive"))
      (node (ref "JP2") (pin "1") (pinfunction "1_1") (pintype "passive"))
    )
  )
)
